# VoltMeter.net
KiCad netlist of a schematic drawn in EAGLE
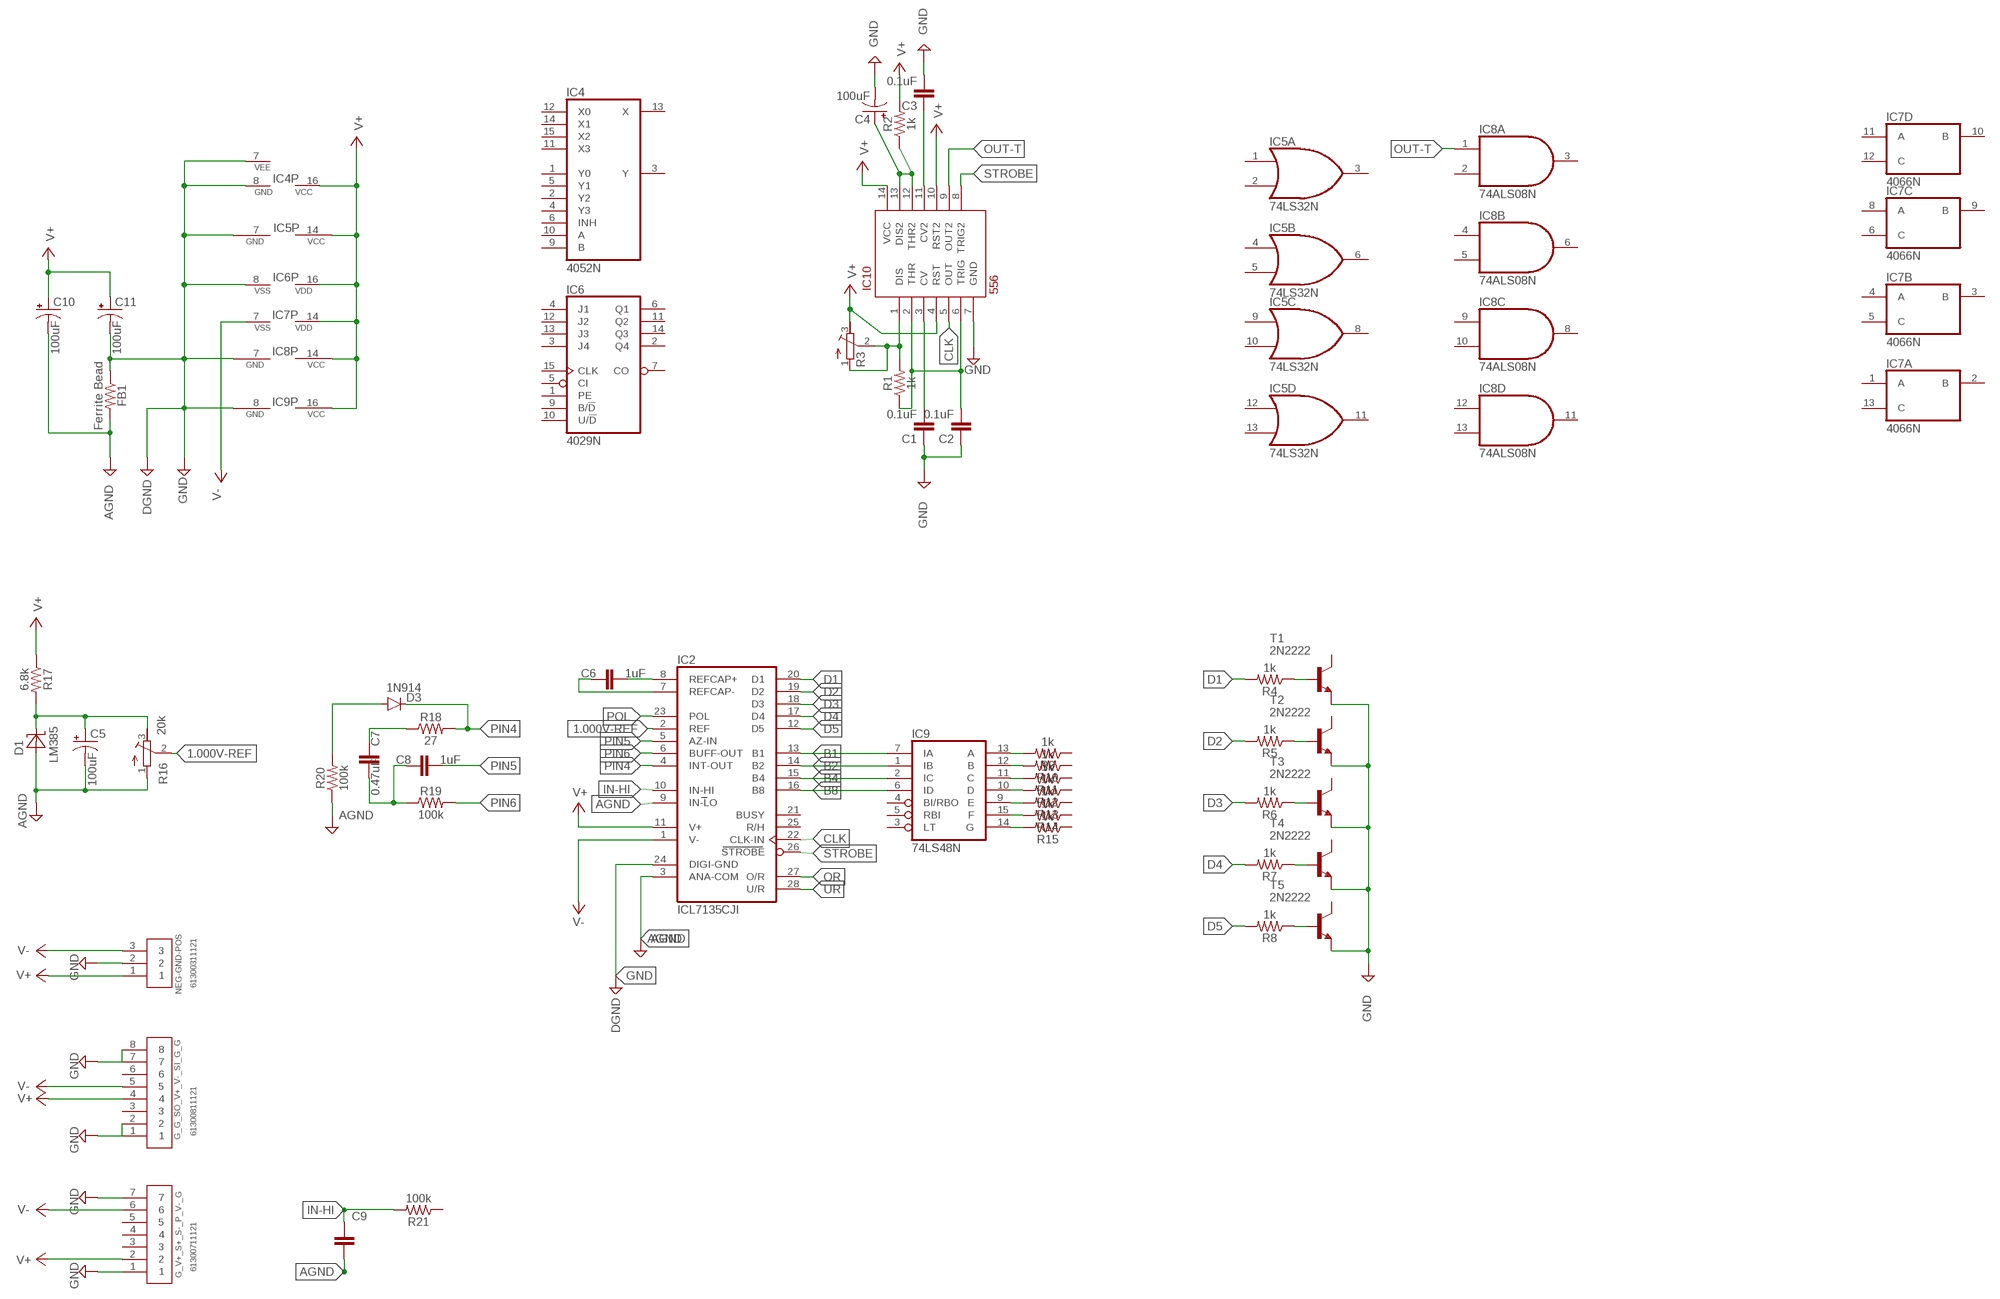
[diagram p0: schematic, sheet 1]

(export (version "E")
  (design (tool "Eeschema 10.0.6"))
  (components
    (comp (ref "C1")
      (value "0.1uF")
      (footprint "eagle-import:CAP-PTH-SMALL-KIT")
      (libsource (lib "eagle-import") (part "0.1UF-KIT-EZ-50V-20%"))
    )
    (comp (ref "C2")
      (value "0.1uF")
      (footprint "eagle-import:CAP-PTH-SMALL-KIT")
      (libsource (lib "eagle-import") (part "0.1UF-KIT-EZ-50V-20%"))
    )
    (comp (ref "C3")
      (value "0.1uF")
      (footprint "eagle-import:CAP-PTH-SMALL-KIT")
      (libsource (lib "eagle-import") (part "0.1UF-KIT-EZ-50V-20%"))
    )
    (comp (ref "C4")
      (value "100uF")
      (footprint "eagle-import:CPOL-RADIAL-2.5MM-6.5MM")
      (libsource (lib "eagle-import") (part "100UF-POLAR-RADIAL-2.5MM-25V-20%"))
    )
    (comp (ref "C5")
      (value "100uF")
      (footprint "eagle-import:CPOL-RADIAL-2.5MM-6.5MM")
      (libsource (lib "eagle-import") (part "100UF-POLAR-RADIAL-2.5MM-25V-20%"))
    )
    (comp (ref "C6")
      (value "1uF")
      (footprint "eagle-import:CAP-PTH-SMALL-KIT")
      (libsource (lib "eagle-import") (part "0.1UF-KIT-EZ-50V-20%"))
    )
    (comp (ref "C7")
      (value "0.47uF")
      (footprint "eagle-import:CAP-PTH-SMALL-KIT")
      (libsource (lib "eagle-import") (part "0.1UF-KIT-EZ-50V-20%"))
    )
    (comp (ref "C8")
      (value "1uF")
      (footprint "eagle-import:CAP-PTH-SMALL-KIT")
      (libsource (lib "eagle-import") (part "0.1UF-KIT-EZ-50V-20%"))
    )
    (comp (ref "C9")
      (value "0.1uF")
      (footprint "eagle-import:C5B2.5")
      (libsource (lib "eagle-import") (part "C5/2.5"))
    )
    (comp (ref "C10")
      (value "100uF")
      (footprint "eagle-import:CPOL-RADIAL-2.5MM-6.5MM")
      (libsource (lib "eagle-import") (part "100UF-POLAR-RADIAL-2.5MM-25V-20%"))
    )
    (comp (ref "C11")
      (value "100uF")
      (footprint "eagle-import:CPOL-RADIAL-2.5MM-6.5MM")
      (libsource (lib "eagle-import") (part "100UF-POLAR-RADIAL-2.5MM-25V-20%"))
    )
    (comp (ref "D1")
      (value "LM385")
      (footprint "eagle-import:TO-92")
      (libsource (lib "eagle-import") (part "LM385"))
    )
    (comp (ref "D3")
      (value "1N914")
      (footprint "eagle-import:DO35-7")
      (libsource (lib "eagle-import") (part "1N4148DO35-7"))
    )
    (comp (ref "FB1")
      (value "Ferrite Bead")
      (footprint "eagle-import:AXIAL-0.3")
      (libsource (lib "eagle-import") (part "1KOHM-HORIZ-1/4W-5%"))
    )
    (comp (ref "G_G_SO_V+_V-_SI_G_G")
      (value "61300811121")
      (footprint "eagle-import:61300811121")
      (fields
        (field (name "DIGI_KEY_PART_NUMBER") "732-5321-ND")
        (field (name "MANUFACTURER") "Wurth Electronics Inc.")
        (field (name "CREATED_BY") "PCBLayout.com")
      )
      (libsource (lib "eagle-import") (part "61300811121"))
    )
    (comp (ref "G_V+_S+_S-_P_V-_G")
      (value "61300711121")
      (footprint "eagle-import:61300711121")
      (fields
        (field (name "DIGI_KEY_PART_NUMBER") "732-5320-ND")
        (field (name "MANUFACTURER") "Wurth Electronics Inc.")
        (field (name "CREATED_BY") "PCBLayout.com")
      )
      (libsource (lib "eagle-import") (part "61300711121"))
    )
    (comp (ref "IC2")
      (value "ICL7135CJI")
      (footprint "eagle-import:DIL28-6")
      (libsource (lib "eagle-import") (part "ICL7135CJI"))
    )
    (comp (ref "IC4")
      (value "4052N")
      (footprint "eagle-import:DIL16")
      (libsource (lib "eagle-import") (part "4052N"))
    )
    (comp (ref "IC5")
      (value "74LS32N")
      (footprint "eagle-import:DIL14")
      (libsource (lib "eagle-import") (part "7432NLS"))
    )
    (comp (ref "IC6")
      (value "4029N")
      (footprint "eagle-import:DIL16")
      (libsource (lib "eagle-import") (part "4029N"))
    )
    (comp (ref "IC7")
      (value "4066N")
      (footprint "eagle-import:DIL14")
      (libsource (lib "eagle-import") (part "4066N"))
    )
    (comp (ref "IC8")
      (value "74ALS08N")
      (footprint "eagle-import:DIL14")
      (libsource (lib "eagle-import") (part "7408NALS"))
    )
    (comp (ref "IC9")
      (value "74LS48N")
      (footprint "eagle-import:DIL16")
      (libsource (lib "eagle-import") (part "7448NLS"))
    )
    (comp (ref "IC10")
      (value "556")
      (footprint "eagle-import:DIP14")
      (libsource (lib "eagle-import") (part "556"))
    )
    (comp (ref "NEG-GND-POS")
      (value "61300311121")
      (footprint "eagle-import:61300311121")
      (fields
        (field (name "DIGI_KEY_PART_NUMBER") "732-5316-ND")
        (field (name "MANUFACTURER") "Wurth Electronics Inc.")
        (field (name "CREATED_BY") "PCBLayout.com")
      )
      (libsource (lib "eagle-import") (part "61300311121"))
    )
    (comp (ref "R1")
      (value "1k")
      (footprint "eagle-import:AXIAL-0.3")
      (libsource (lib "eagle-import") (part "1KOHM-HORIZ-1/4W-1%"))
    )
    (comp (ref "R2")
      (value "1k")
      (footprint "eagle-import:AXIAL-0.3")
      (libsource (lib "eagle-import") (part "1KOHM-HORIZ-1/4W-1%"))
    )
    (comp (ref "R3")
      (value "R-TRIMM3299W")
      (footprint "eagle-import:RTRIM3299W")
      (libsource (lib "eagle-import") (part "R-TRIMM3299W"))
    )
    (comp (ref "R4")
      (value "1k")
      (footprint "eagle-import:AXIAL-0.3")
      (libsource (lib "eagle-import") (part "1KOHM-HORIZ-1/4W-1%"))
    )
    (comp (ref "R5")
      (value "1k")
      (footprint "eagle-import:AXIAL-0.3")
      (libsource (lib "eagle-import") (part "1KOHM-HORIZ-1/4W-1%"))
    )
    (comp (ref "R6")
      (value "1k")
      (footprint "eagle-import:AXIAL-0.3")
      (libsource (lib "eagle-import") (part "1KOHM-HORIZ-1/4W-1%"))
    )
    (comp (ref "R7")
      (value "1k")
      (footprint "eagle-import:AXIAL-0.3")
      (libsource (lib "eagle-import") (part "1KOHM-HORIZ-1/4W-1%"))
    )
    (comp (ref "R8")
      (value "1k")
      (footprint "eagle-import:AXIAL-0.3")
      (libsource (lib "eagle-import") (part "1KOHM-HORIZ-1/4W-1%"))
    )
    (comp (ref "R9")
      (value "1k")
      (footprint "eagle-import:AXIAL-0.3")
      (libsource (lib "eagle-import") (part "1KOHM-HORIZ-1/4W-1%"))
    )
    (comp (ref "R10")
      (value "1k")
      (footprint "eagle-import:AXIAL-0.3")
      (libsource (lib "eagle-import") (part "1KOHM-HORIZ-1/4W-1%"))
    )
    (comp (ref "R11")
      (value "1k")
      (footprint "eagle-import:AXIAL-0.3")
      (libsource (lib "eagle-import") (part "1KOHM-HORIZ-1/4W-1%"))
    )
    (comp (ref "R12")
      (value "1k")
      (footprint "eagle-import:AXIAL-0.3")
      (libsource (lib "eagle-import") (part "1KOHM-HORIZ-1/4W-1%"))
    )
    (comp (ref "R13")
      (value "1k")
      (footprint "eagle-import:AXIAL-0.3")
      (libsource (lib "eagle-import") (part "1KOHM-HORIZ-1/4W-1%"))
    )
    (comp (ref "R14")
      (value "1k")
      (footprint "eagle-import:AXIAL-0.3")
      (libsource (lib "eagle-import") (part "1KOHM-HORIZ-1/4W-1%"))
    )
    (comp (ref "R15")
      (value "1k")
      (footprint "eagle-import:AXIAL-0.3")
      (libsource (lib "eagle-import") (part "1KOHM-HORIZ-1/4W-1%"))
    )
    (comp (ref "R16")
      (value "20k")
      (footprint "eagle-import:RTRIM3299W")
      (libsource (lib "eagle-import") (part "R-TRIMM3299W"))
    )
    (comp (ref "R17")
      (value "6.8k")
      (footprint "eagle-import:AXIAL-0.3")
      (libsource (lib "eagle-import") (part "1KOHM-HORIZ-1/4W-1%"))
    )
    (comp (ref "R18")
      (value "27")
      (footprint "eagle-import:AXIAL-0.3")
      (libsource (lib "eagle-import") (part "1KOHM-HORIZ-1/4W-1%"))
    )
    (comp (ref "R19")
      (value "100k")
      (footprint "eagle-import:AXIAL-0.3")
      (libsource (lib "eagle-import") (part "1KOHM-HORIZ-1/4W-1%"))
    )
    (comp (ref "R20")
      (value "100k")
      (footprint "eagle-import:AXIAL-0.3")
      (libsource (lib "eagle-import") (part "1KOHM-HORIZ-1/4W-1%"))
    )
    (comp (ref "R21")
      (value "100k")
      (footprint "eagle-import:AXIAL-0.3")
      (libsource (lib "eagle-import") (part "1KOHM-HORIZ-1/4W-1%"))
    )
    (comp (ref "T1")
      (value "2N2222")
      (footprint "eagle-import:TO92-EBC-OVAL")
      (libsource (lib "eagle-import") (part "2N2222"))
    )
    (comp (ref "T2")
      (value "2N2222")
      (footprint "eagle-import:TO92-EBC-OVAL")
      (libsource (lib "eagle-import") (part "2N2222"))
    )
    (comp (ref "T3")
      (value "2N2222")
      (footprint "eagle-import:TO92-EBC-OVAL")
      (libsource (lib "eagle-import") (part "2N2222"))
    )
    (comp (ref "T4")
      (value "2N2222")
      (footprint "eagle-import:TO92-EBC-OVAL")
      (libsource (lib "eagle-import") (part "2N2222"))
    )
    (comp (ref "T5")
      (value "2N2222")
      (footprint "eagle-import:TO92-EBC-OVAL")
      (libsource (lib "eagle-import") (part "2N2222"))
    )
  )
  (nets
    (net (code "1") (name "1.000V-REF") (class "Default")
      (node (ref "IC2") (pin "2") (pinfunction "REF_2") (pintype "input"))
      (node (ref "R16") (pin "2") (pinfunction "S_2") (pintype "passive"))
    )
    (net (code "2") (name "AGND") (class "Default")
      (node (ref "C10") (pin "2") (pinfunction "-_2") (pintype "passive"))
      (node (ref "C5") (pin "2") (pinfunction "-_2") (pintype "passive"))
      (node (ref "C9") (pin "2") (pinfunction "2_2") (pintype "passive"))
      (node (ref "D1") (pin "+") (pinfunction "+_+") (pintype "passive"))
      (node (ref "FB1") (pin "P$2") (pinfunction "2_P$2") (pintype "passive"))
      (node (ref "IC2") (pin "3") (pinfunction "ANA-COM_3") (pintype "power_in"))
      (node (ref "IC2") (pin "9") (pinfunction "IN-LO_9") (pintype "input"))
      (node (ref "R16") (pin "1") (pinfunction "A_1") (pintype "passive"))
      (node (ref "R20") (pin "P$1") (pinfunction "1_P$1") (pintype "passive"))
    )
    (net (code "3") (name "B1") (class "Default")
      (node (ref "IC2") (pin "13") (pinfunction "B1_13") (pintype "output"))
      (node (ref "IC9") (pin "7") (pinfunction "IA_7") (pintype "input"))
    )
    (net (code "4") (name "B2") (class "Default")
      (node (ref "IC2") (pin "14") (pinfunction "B2_14") (pintype "output"))
      (node (ref "IC9") (pin "1") (pinfunction "IB_1") (pintype "input"))
    )
    (net (code "5") (name "B4") (class "Default")
      (node (ref "IC2") (pin "15") (pinfunction "B4_15") (pintype "output"))
      (node (ref "IC9") (pin "2") (pinfunction "IC_2") (pintype "input"))
    )
    (net (code "6") (name "B8") (class "Default")
      (node (ref "IC2") (pin "16") (pinfunction "B8_16") (pintype "output"))
      (node (ref "IC9") (pin "6") (pinfunction "ID_6") (pintype "input"))
    )
    (net (code "7") (name "CLK") (class "Default")
      (node (ref "IC10") (pin "5") (pinfunction "OUT_5") (pintype "bidirectional"))
      (node (ref "IC2") (pin "22") (pinfunction "CLK-IN_22") (pintype "input"))
    )
    (net (code "8") (name "D1") (class "Default")
      (node (ref "IC2") (pin "20") (pinfunction "D1_20") (pintype "tri_state"))
      (node (ref "R4") (pin "P$2") (pinfunction "2_P$2") (pintype "passive"))
    )
    (net (code "9") (name "D2") (class "Default")
      (node (ref "IC2") (pin "19") (pinfunction "D2_19") (pintype "tri_state"))
      (node (ref "R5") (pin "P$2") (pinfunction "2_P$2") (pintype "passive"))
    )
    (net (code "10") (name "D3") (class "Default")
      (node (ref "IC2") (pin "18") (pinfunction "D3_18") (pintype "tri_state"))
      (node (ref "R6") (pin "P$2") (pinfunction "2_P$2") (pintype "passive"))
    )
    (net (code "11") (name "D4") (class "Default")
      (node (ref "IC2") (pin "17") (pinfunction "D4_17") (pintype "tri_state"))
      (node (ref "R7") (pin "P$2") (pinfunction "2_P$2") (pintype "passive"))
    )
    (net (code "12") (name "D5") (class "Default")
      (node (ref "IC2") (pin "12") (pinfunction "D5_12") (pintype "tri_state"))
      (node (ref "R8") (pin "P$2") (pinfunction "2_P$2") (pintype "passive"))
    )
    (net (code "13") (name "GND") (class "Default")
      (node (ref "C1") (pin "1") (pinfunction "1_1") (pintype "passive"))
      (node (ref "C11") (pin "2") (pinfunction "-_2") (pintype "passive"))
      (node (ref "C2") (pin "1") (pinfunction "1_1") (pintype "passive"))
      (node (ref "C3") (pin "2") (pinfunction "2_2") (pintype "passive"))
      (node (ref "C4") (pin "2") (pinfunction "-_2") (pintype "passive"))
      (node (ref "FB1") (pin "P$1") (pinfunction "1_P$1") (pintype "passive"))
      (node (ref "G_G_SO_V+_V-_SI_G_G") (pin "1") (pinfunction "1_1") (pintype "passive"))
      (node (ref "G_G_SO_V+_V-_SI_G_G") (pin "2") (pinfunction "2_2") (pintype "passive"))
      (node (ref "G_G_SO_V+_V-_SI_G_G") (pin "7") (pinfunction "7_7") (pintype "passive"))
      (node (ref "G_G_SO_V+_V-_SI_G_G") (pin "8") (pinfunction "8_8") (pintype "passive"))
      (node (ref "G_V+_S+_S-_P_V-_G") (pin "1") (pinfunction "1_1") (pintype "passive"))
      (node (ref "G_V+_S+_S-_P_V-_G") (pin "7") (pinfunction "7_7") (pintype "passive"))
      (node (ref "IC10") (pin "7") (pinfunction "GND_7") (pintype "bidirectional"))
      (node (ref "IC2") (pin "24") (pinfunction "DIGI-GND_24") (pintype "power_in"))
      (node (ref "IC4") (pin "7") (pinfunction "VEE_7") (pintype "power_in"))
      (node (ref "IC4") (pin "8") (pinfunction "GND_8") (pintype "power_in"))
      (node (ref "IC5") (pin "7") (pinfunction "GND_7") (pintype "power_in"))
      (node (ref "IC6") (pin "8") (pinfunction "VSS_8") (pintype "power_in"))
      (node (ref "IC8") (pin "7") (pinfunction "GND_7") (pintype "power_in"))
      (node (ref "IC9") (pin "8") (pinfunction "GND_8") (pintype "power_in"))
      (node (ref "NEG-GND-POS") (pin "2") (pinfunction "2_2") (pintype "passive"))
      (node (ref "T1") (pin "E") (pinfunction "E_E") (pintype "passive"))
      (node (ref "T2") (pin "E") (pinfunction "E_E") (pintype "passive"))
      (node (ref "T3") (pin "E") (pinfunction "E_E") (pintype "passive"))
      (node (ref "T4") (pin "E") (pinfunction "E_E") (pintype "passive"))
      (node (ref "T5") (pin "E") (pinfunction "E_E") (pintype "passive"))
    )
    (net (code "14") (name "IN-HI") (class "Default")
      (node (ref "C9") (pin "1") (pinfunction "1_1") (pintype "passive"))
      (node (ref "IC2") (pin "10") (pinfunction "IN-HI_10") (pintype "input"))
      (node (ref "R21") (pin "P$2") (pinfunction "2_P$2") (pintype "passive"))
    )
    (net (code "15") (name "Net-(C4-+)") (class "Default")
      (node (ref "C4") (pin "1") (pinfunction "+_1") (pintype "passive"))
      (node (ref "IC10") (pin "12") (pinfunction "THR2_12") (pintype "bidirectional"))
      (node (ref "IC10") (pin "13") (pinfunction "DIS2_13") (pintype "bidirectional"))
      (node (ref "R2") (pin "P$1") (pinfunction "1_P$1") (pintype "passive"))
    )
    (net (code "16") (name "Net-(C5-+)") (class "Default")
      (node (ref "C5") (pin "1") (pinfunction "+_1") (pintype "passive"))
      (node (ref "D1") (pin "-") (pinfunction "-_-") (pintype "passive"))
      (node (ref "R16") (pin "3") (pinfunction "E_3") (pintype "passive"))
      (node (ref "R17") (pin "P$2") (pinfunction "2_P$2") (pintype "passive"))
    )
    (net (code "17") (name "Net-(IC2-REFCAP+)") (class "Default")
      (node (ref "C6") (pin "2") (pinfunction "2_2") (pintype "passive"))
      (node (ref "IC2") (pin "8") (pinfunction "REFCAP+_8") (pintype "passive"))
    )
    (net (code "18") (name "Net-(IC2-REFCAP-)") (class "Default")
      (node (ref "C6") (pin "1") (pinfunction "1_1") (pintype "passive"))
      (node (ref "IC2") (pin "7") (pinfunction "REFCAP-_7") (pintype "passive"))
    )
    (net (code "19") (name "Net-(IC9A-A)") (class "Default")
      (node (ref "IC9") (pin "13") (pinfunction "A_13") (pintype "output"))
      (node (ref "R9") (pin "P$2") (pinfunction "2_P$2") (pintype "passive"))
    )
    (net (code "20") (name "Net-(IC9A-B)") (class "Default")
      (node (ref "IC9") (pin "12") (pinfunction "B_12") (pintype "output"))
      (node (ref "R10") (pin "P$2") (pinfunction "2_P$2") (pintype "passive"))
    )
    (net (code "21") (name "Net-(IC9A-C)") (class "Default")
      (node (ref "IC9") (pin "11") (pinfunction "C_11") (pintype "output"))
      (node (ref "R11") (pin "P$2") (pinfunction "2_P$2") (pintype "passive"))
    )
    (net (code "22") (name "Net-(IC9A-D)") (class "Default")
      (node (ref "IC9") (pin "10") (pinfunction "D_10") (pintype "output"))
      (node (ref "R12") (pin "P$2") (pinfunction "2_P$2") (pintype "passive"))
    )
    (net (code "23") (name "Net-(IC9A-E)") (class "Default")
      (node (ref "IC9") (pin "9") (pinfunction "E_9") (pintype "output"))
      (node (ref "R13") (pin "P$2") (pinfunction "2_P$2") (pintype "passive"))
    )
    (net (code "24") (name "Net-(IC9A-F)") (class "Default")
      (node (ref "IC9") (pin "15") (pinfunction "F_15") (pintype "output"))
      (node (ref "R14") (pin "P$2") (pinfunction "2_P$2") (pintype "passive"))
    )
    (net (code "25") (name "Net-(IC9A-G)") (class "Default")
      (node (ref "IC9") (pin "14") (pinfunction "G_14") (pintype "output"))
      (node (ref "R15") (pin "P$2") (pinfunction "2_P$2") (pintype "passive"))
    )
    (net (code "26") (name "Net-(IC10-CV)") (class "Default")
      (node (ref "C1") (pin "2") (pinfunction "2_2") (pintype "passive"))
      (node (ref "IC10") (pin "3") (pinfunction "CV_3") (pintype "bidirectional"))
    )
    (net (code "27") (name "Net-(IC10-CV2)") (class "Default")
      (node (ref "C3") (pin "1") (pinfunction "1_1") (pintype "passive"))
      (node (ref "IC10") (pin "11") (pinfunction "CV2_11") (pintype "bidirectional"))
    )
    (net (code "28") (name "Net-(IC10-DIS)") (class "Default")
      (node (ref "IC10") (pin "1") (pinfunction "DIS_1") (pintype "bidirectional"))
      (node (ref "R1") (pin "P$2") (pinfunction "2_P$2") (pintype "passive"))
      (node (ref "R3") (pin "1") (pinfunction "A_1") (pintype "passive"))
      (node (ref "R3") (pin "2") (pinfunction "S_2") (pintype "passive"))
    )
    (net (code "29") (name "Net-(IC10-THR)") (class "Default")
      (node (ref "C2") (pin "2") (pinfunction "2_2") (pintype "passive"))
      (node (ref "IC10") (pin "2") (pinfunction "THR_2") (pintype "bidirectional"))
      (node (ref "IC10") (pin "6") (pinfunction "TRIG_6") (pintype "bidirectional"))
      (node (ref "R1") (pin "P$1") (pinfunction "1_P$1") (pintype "passive"))
    )
    (net (code "30") (name "Net-(R4-1)") (class "Default")
      (node (ref "R4") (pin "P$1") (pinfunction "1_P$1") (pintype "passive"))
      (node (ref "T1") (pin "B") (pinfunction "B_B") (pintype "passive"))
    )
    (net (code "31") (name "Net-(R5-1)") (class "Default")
      (node (ref "R5") (pin "P$1") (pinfunction "1_P$1") (pintype "passive"))
      (node (ref "T2") (pin "B") (pinfunction "B_B") (pintype "passive"))
    )
    (net (code "32") (name "Net-(R6-1)") (class "Default")
      (node (ref "R6") (pin "P$1") (pinfunction "1_P$1") (pintype "passive"))
      (node (ref "T3") (pin "B") (pinfunction "B_B") (pintype "passive"))
    )
    (net (code "33") (name "Net-(R7-1)") (class "Default")
      (node (ref "R7") (pin "P$1") (pinfunction "1_P$1") (pintype "passive"))
      (node (ref "T4") (pin "B") (pinfunction "B_B") (pintype "passive"))
    )
    (net (code "34") (name "Net-(R8-1)") (class "Default")
      (node (ref "R8") (pin "P$1") (pinfunction "1_P$1") (pintype "passive"))
      (node (ref "T5") (pin "B") (pinfunction "B_B") (pintype "passive"))
    )
    (net (code "35") (name "Net-(R18-1)") (class "Default")
      (node (ref "C7") (pin "1") (pinfunction "1_1") (pintype "passive"))
      (node (ref "R18") (pin "P$1") (pinfunction "1_P$1") (pintype "passive"))
    )
    (net (code "36") (name "Net-(R19-1)") (class "Default")
      (node (ref "C7") (pin "2") (pinfunction "2_2") (pintype "passive"))
      (node (ref "C8") (pin "1") (pinfunction "1_1") (pintype "passive"))
      (node (ref "R19") (pin "P$1") (pinfunction "1_P$1") (pintype "passive"))
    )
    (net (code "37") (name "Net-(R20-2)") (class "Default")
      (node (ref "D3") (pin "A") (pinfunction "A_A") (pintype "passive"))
      (node (ref "R20") (pin "P$2") (pinfunction "2_P$2") (pintype "passive"))
    )
    (net (code "38") (name "OR") (class "Default")
      (node (ref "IC2") (pin "27") (pinfunction "O/R_27") (pintype "output"))
    )
    (net (code "39") (name "OUT-T") (class "Default")
      (node (ref "IC10") (pin "9") (pinfunction "OUT2_9") (pintype "bidirectional"))
      (node (ref "IC8") (pin "1") (pinfunction "I0_1") (pintype "input"))
    )
    (net (code "40") (name "PIN4") (class "Default")
      (node (ref "D3") (pin "C") (pinfunction "C_C") (pintype "passive"))
      (node (ref "IC2") (pin "4") (pinfunction "INT-OUT_4") (pintype "output"))
      (node (ref "R18") (pin "P$2") (pinfunction "2_P$2") (pintype "passive"))
    )
    (net (code "41") (name "PIN5") (class "Default")
      (node (ref "C8") (pin "2") (pinfunction "2_2") (pintype "passive"))
      (node (ref "IC2") (pin "5") (pinfunction "AZ-IN_5") (pintype "input"))
    )
    (net (code "42") (name "PIN6") (class "Default")
      (node (ref "IC2") (pin "6") (pinfunction "BUFF-OUT_6") (pintype "output"))
      (node (ref "R19") (pin "P$2") (pinfunction "2_P$2") (pintype "passive"))
    )
    (net (code "43") (name "POL") (class "Default")
      (node (ref "IC2") (pin "23") (pinfunction "POL_23") (pintype "input"))
    )
    (net (code "44") (name "STROBE") (class "Default")
      (node (ref "IC10") (pin "8") (pinfunction "TRIG2_8") (pintype "bidirectional"))
      (node (ref "IC2") (pin "26") (pinfunction "STROBE_26") (pintype "output"))
    )
    (net (code "45") (name "UR") (class "Default")
      (node (ref "IC2") (pin "28") (pinfunction "U/R_28") (pintype "output"))
    )
    (net (code "46") (name "V+") (class "Default")
      (node (ref "C10") (pin "1") (pinfunction "+_1") (pintype "passive"))
      (node (ref "C11") (pin "1") (pinfunction "+_1") (pintype "passive"))
      (node (ref "G_G_SO_V+_V-_SI_G_G") (pin "4") (pinfunction "4_4") (pintype "passive"))
      (node (ref "G_V+_S+_S-_P_V-_G") (pin "2") (pinfunction "2_2") (pintype "passive"))
      (node (ref "IC10") (pin "10") (pinfunction "RST2_10") (pintype "bidirectional"))
      (node (ref "IC10") (pin "14") (pinfunction "VCC_14") (pintype "bidirectional"))
      (node (ref "IC10") (pin "4") (pinfunction "RST_4") (pintype "bidirectional"))
      (node (ref "IC2") (pin "11") (pinfunction "V+_11") (pintype "power_in"))
      (node (ref "IC4") (pin "16") (pinfunction "VCC_16") (pintype "power_in"))
      (node (ref "IC5") (pin "14") (pinfunction "VCC_14") (pintype "power_in"))
      (node (ref "IC6") (pin "16") (pinfunction "VDD_16") (pintype "power_in"))
      (node (ref "IC7") (pin "14") (pinfunction "VDD_14") (pintype "power_in"))
      (node (ref "IC8") (pin "14") (pinfunction "VCC_14") (pintype "power_in"))
      (node (ref "IC9") (pin "16") (pinfunction "VCC_16") (pintype "power_in"))
      (node (ref "NEG-GND-POS") (pin "1") (pinfunction "1_1") (pintype "passive"))
      (node (ref "R17") (pin "P$1") (pinfunction "1_P$1") (pintype "passive"))
      (node (ref "R2") (pin "P$2") (pinfunction "2_P$2") (pintype "passive"))
      (node (ref "R3") (pin "3") (pinfunction "E_3") (pintype "passive"))
    )
    (net (code "47") (name "V-") (class "Default")
      (node (ref "G_G_SO_V+_V-_SI_G_G") (pin "5") (pinfunction "5_5") (pintype "passive"))
      (node (ref "G_V+_S+_S-_P_V-_G") (pin "6") (pinfunction "6_6") (pintype "passive"))
      (node (ref "IC2") (pin "1") (pinfunction "V-_1") (pintype "power_in"))
      (node (ref "IC7") (pin "7") (pinfunction "VSS_7") (pintype "power_in"))
      (node (ref "NEG-GND-POS") (pin "3") (pinfunction "3_3") (pintype "passive"))
    )
    (net (code "48") (name "unconnected-(G_G_SO_V+_V-_SI_G_G-Pad3)") (class "Default")
      (node (ref "G_G_SO_V+_V-_SI_G_G") (pin "3") (pinfunction "3_3") (pintype "passive"))
    )
    (net (code "49") (name "unconnected-(G_G_SO_V+_V-_SI_G_G-Pad6)") (class "Default")
      (node (ref "G_G_SO_V+_V-_SI_G_G") (pin "6") (pinfunction "6_6") (pintype "passive"))
    )
    (net (code "50") (name "unconnected-(G_V+_S+_S-_P_V-_G-Pad3)") (class "Default")
      (node (ref "G_V+_S+_S-_P_V-_G") (pin "3") (pinfunction "3_3") (pintype "passive"))
    )
    (net (code "51") (name "unconnected-(G_V+_S+_S-_P_V-_G-Pad4)") (class "Default")
      (node (ref "G_V+_S+_S-_P_V-_G") (pin "4") (pinfunction "4_4") (pintype "passive"))
    )
    (net (code "52") (name "unconnected-(G_V+_S+_S-_P_V-_G-Pad5)") (class "Default")
      (node (ref "G_V+_S+_S-_P_V-_G") (pin "5") (pinfunction "5_5") (pintype "passive"))
    )
    (net (code "53") (name "unconnected-(IC2-BUSY-Pad21)") (class "Default")
      (node (ref "IC2") (pin "21") (pinfunction "BUSY_21") (pintype "output"))
    )
    (net (code "54") (name "unconnected-(IC2-R{slash}H-Pad25)") (class "Default")
      (node (ref "IC2") (pin "25") (pinfunction "R/H_25") (pintype "input"))
    )
    (net (code "55") (name "unconnected-(IC4A-A-Pad10)") (class "Default")
      (node (ref "IC4") (pin "10") (pinfunction "A_10") (pintype "input"))
    )
    (net (code "56") (name "unconnected-(IC4A-B-Pad9)") (class "Default")
      (node (ref "IC4") (pin "9") (pinfunction "B_9") (pintype "input"))
    )
    (net (code "57") (name "unconnected-(IC4A-INH-Pad6)") (class "Default")
      (node (ref "IC4") (pin "6") (pinfunction "INH_6") (pintype "input"))
    )
    (net (code "58") (name "unconnected-(IC4A-X-Pad13)") (class "Default")
      (node (ref "IC4") (pin "13") (pinfunction "X_13") (pintype "bidirectional"))
    )
    (net (code "59") (name "unconnected-(IC4A-X0-Pad12)") (class "Default")
      (node (ref "IC4") (pin "12") (pinfunction "X0_12") (pintype "bidirectional"))
    )
    (net (code "60") (name "unconnected-(IC4A-X1-Pad14)") (class "Default")
      (node (ref "IC4") (pin "14") (pinfunction "X1_14") (pintype "bidirectional"))
    )
    (net (code "61") (name "unconnected-(IC4A-X2-Pad15)") (class "Default")
      (node (ref "IC4") (pin "15") (pinfunction "X2_15") (pintype "bidirectional"))
    )
    (net (code "62") (name "unconnected-(IC4A-X3-Pad11)") (class "Default")
      (node (ref "IC4") (pin "11") (pinfunction "X3_11") (pintype "bidirectional"))
    )
    (net (code "63") (name "unconnected-(IC4A-Y-Pad3)") (class "Default")
      (node (ref "IC4") (pin "3") (pinfunction "Y_3") (pintype "bidirectional"))
    )
    (net (code "64") (name "unconnected-(IC4A-Y0-Pad1)") (class "Default")
      (node (ref "IC4") (pin "1") (pinfunction "Y0_1") (pintype "bidirectional"))
    )
    (net (code "65") (name "unconnected-(IC4A-Y1-Pad5)") (class "Default")
      (node (ref "IC4") (pin "5") (pinfunction "Y1_5") (pintype "bidirectional"))
    )
    (net (code "66") (name "unconnected-(IC4A-Y2-Pad2)") (class "Default")
      (node (ref "IC4") (pin "2") (pinfunction "Y2_2") (pintype "bidirectional"))
    )
    (net (code "67") (name "unconnected-(IC4A-Y3-Pad4)") (class "Default")
      (node (ref "IC4") (pin "4") (pinfunction "Y3_4") (pintype "bidirectional"))
    )
    (net (code "68") (name "unconnected-(IC5A-I0-Pad1)") (class "Default")
      (node (ref "IC5") (pin "1") (pinfunction "I0_1") (pintype "input"))
    )
    (net (code "69") (name "unconnected-(IC5A-I1-Pad2)") (class "Default")
      (node (ref "IC5") (pin "2") (pinfunction "I1_2") (pintype "input"))
    )
    (net (code "70") (name "unconnected-(IC5A-O-Pad3)") (class "Default")
      (node (ref "IC5") (pin "3") (pinfunction "O_3") (pintype "output"))
    )
    (net (code "71") (name "unconnected-(IC5B-I0-Pad4)") (class "Default")
      (node (ref "IC5") (pin "4") (pinfunction "I0_4") (pintype "input"))
    )
    (net (code "72") (name "unconnected-(IC5B-I1-Pad5)") (class "Default")
      (node (ref "IC5") (pin "5") (pinfunction "I1_5") (pintype "input"))
    )
    (net (code "73") (name "unconnected-(IC5B-O-Pad6)") (class "Default")
      (node (ref "IC5") (pin "6") (pinfunction "O_6") (pintype "output"))
    )
    (net (code "74") (name "unconnected-(IC5C-I0-Pad9)") (class "Default")
      (node (ref "IC5") (pin "9") (pinfunction "I0_9") (pintype "input"))
    )
    (net (code "75") (name "unconnected-(IC5C-I1-Pad10)") (class "Default")
      (node (ref "IC5") (pin "10") (pinfunction "I1_10") (pintype "input"))
    )
    (net (code "76") (name "unconnected-(IC5C-O-Pad8)") (class "Default")
      (node (ref "IC5") (pin "8") (pinfunction "O_8") (pintype "output"))
    )
    (net (code "77") (name "unconnected-(IC5D-I0-Pad12)") (class "Default")
      (node (ref "IC5") (pin "12") (pinfunction "I0_12") (pintype "input"))
    )
    (net (code "78") (name "unconnected-(IC5D-I1-Pad13)") (class "Default")
      (node (ref "IC5") (pin "13") (pinfunction "I1_13") (pintype "input"))
    )
    (net (code "79") (name "unconnected-(IC5D-O-Pad11)") (class "Default")
      (node (ref "IC5") (pin "11") (pinfunction "O_11") (pintype "output"))
    )
    (net (code "80") (name "unconnected-(IC6A-B{slash}~{D}-Pad9)") (class "Default")
      (node (ref "IC6") (pin "9") (pinfunction "B/~{D}_9") (pintype "input"))
    )
    (net (code "81") (name "unconnected-(IC6A-CI-Pad5)") (class "Default")
      (node (ref "IC6") (pin "5") (pinfunction "CI_5") (pintype "input"))
    )
    (net (code "82") (name "unconnected-(IC6A-CLK-Pad15)") (class "Default")
      (node (ref "IC6") (pin "15") (pinfunction "CLK_15") (pintype "input"))
    )
    (net (code "83") (name "unconnected-(IC6A-CO-Pad7)") (class "Default")
      (node (ref "IC6") (pin "7") (pinfunction "CO_7") (pintype "output"))
    )
    (net (code "84") (name "unconnected-(IC6A-J1-Pad4)") (class "Default")
      (node (ref "IC6") (pin "4") (pinfunction "J1_4") (pintype "input"))
    )
    (net (code "85") (name "unconnected-(IC6A-J2-Pad12)") (class "Default")
      (node (ref "IC6") (pin "12") (pinfunction "J2_12") (pintype "input"))
    )
    (net (code "86") (name "unconnected-(IC6A-J3-Pad13)") (class "Default")
      (node (ref "IC6") (pin "13") (pinfunction "J3_13") (pintype "input"))
    )
    (net (code "87") (name "unconnected-(IC6A-J4-Pad3)") (class "Default")
      (node (ref "IC6") (pin "3") (pinfunction "J4_3") (pintype "input"))
    )
    (net (code "88") (name "unconnected-(IC6A-PE-Pad1)") (class "Default")
      (node (ref "IC6") (pin "1") (pinfunction "PE_1") (pintype "input"))
    )
    (net (code "89") (name "unconnected-(IC6A-Q1-Pad6)") (class "Default")
      (node (ref "IC6") (pin "6") (pinfunction "Q1_6") (pintype "output"))
    )
    (net (code "90") (name "unconnected-(IC6A-Q2-Pad11)") (class "Default")
      (node (ref "IC6") (pin "11") (pinfunction "Q2_11") (pintype "output"))
    )
    (net (code "91") (name "unconnected-(IC6A-Q3-Pad14)") (class "Default")
      (node (ref "IC6") (pin "14") (pinfunction "Q3_14") (pintype "output"))
    )
    (net (code "92") (name "unconnected-(IC6A-Q4-Pad2)") (class "Default")
      (node (ref "IC6") (pin "2") (pinfunction "Q4_2") (pintype "output"))
    )
    (net (code "93") (name "unconnected-(IC6A-U{slash}~{D}-Pad10)") (class "Default")
      (node (ref "IC6") (pin "10") (pinfunction "U/~{D}_10") (pintype "input"))
    )
    (net (code "94") (name "unconnected-(IC7A-A-Pad1)") (class "Default")
      (node (ref "IC7") (pin "1") (pinfunction "A_1") (pintype "tri_state"))
    )
    (net (code "95") (name "unconnected-(IC7A-B-Pad2)") (class "Default")
      (node (ref "IC7") (pin "2") (pinfunction "B_2") (pintype "tri_state"))
    )
    (net (code "96") (name "unconnected-(IC7A-C-Pad13)") (class "Default")
      (node (ref "IC7") (pin "13") (pinfunction "C_13") (pintype "input"))
    )
    (net (code "97") (name "unconnected-(IC7B-A-Pad4)") (class "Default")
      (node (ref "IC7") (pin "4") (pinfunction "A_4") (pintype "tri_state"))
    )
    (net (code "98") (name "unconnected-(IC7B-B-Pad3)") (class "Default")
      (node (ref "IC7") (pin "3") (pinfunction "B_3") (pintype "tri_state"))
    )
    (net (code "99") (name "unconnected-(IC7B-C-Pad5)") (class "Default")
      (node (ref "IC7") (pin "5") (pinfunction "C_5") (pintype "input"))
    )
    (net (code "100") (name "unconnected-(IC7C-A-Pad8)") (class "Default")
      (node (ref "IC7") (pin "8") (pinfunction "A_8") (pintype "tri_state"))
    )
    (net (code "101") (name "unconnected-(IC7C-B-Pad9)") (class "Default")
      (node (ref "IC7") (pin "9") (pinfunction "B_9") (pintype "tri_state"))
    )
    (net (code "102") (name "unconnected-(IC7C-C-Pad6)") (class "Default")
      (node (ref "IC7") (pin "6") (pinfunction "C_6") (pintype "input"))
    )
    (net (code "103") (name "unconnected-(IC7D-A-Pad11)") (class "Default")
      (node (ref "IC7") (pin "11") (pinfunction "A_11") (pintype "tri_state"))
    )
    (net (code "104") (name "unconnected-(IC7D-B-Pad10)") (class "Default")
      (node (ref "IC7") (pin "10") (pinfunction "B_10") (pintype "tri_state"))
    )
    (net (code "105") (name "unconnected-(IC7D-C-Pad12)") (class "Default")
      (node (ref "IC7") (pin "12") (pinfunction "C_12") (pintype "input"))
    )
    (net (code "106") (name "unconnected-(IC8A-I1-Pad2)") (class "Default")
      (node (ref "IC8") (pin "2") (pinfunction "I1_2") (pintype "input"))
    )
    (net (code "107") (name "unconnected-(IC8A-O-Pad3)") (class "Default")
      (node (ref "IC8") (pin "3") (pinfunction "O_3") (pintype "output"))
    )
    (net (code "108") (name "unconnected-(IC8B-I0-Pad4)") (class "Default")
      (node (ref "IC8") (pin "4") (pinfunction "I0_4") (pintype "input"))
    )
    (net (code "109") (name "unconnected-(IC8B-I1-Pad5)") (class "Default")
      (node (ref "IC8") (pin "5") (pinfunction "I1_5") (pintype "input"))
    )
    (net (code "110") (name "unconnected-(IC8B-O-Pad6)") (class "Default")
      (node (ref "IC8") (pin "6") (pinfunction "O_6") (pintype "output"))
    )
    (net (code "111") (name "unconnected-(IC8C-I0-Pad9)") (class "Default")
      (node (ref "IC8") (pin "9") (pinfunction "I0_9") (pintype "input"))
    )
    (net (code "112") (name "unconnected-(IC8C-I1-Pad10)") (class "Default")
      (node (ref "IC8") (pin "10") (pinfunction "I1_10") (pintype "input"))
    )
    (net (code "113") (name "unconnected-(IC8C-O-Pad8)") (class "Default")
      (node (ref "IC8") (pin "8") (pinfunction "O_8") (pintype "output"))
    )
    (net (code "114") (name "unconnected-(IC8D-I0-Pad12)") (class "Default")
      (node (ref "IC8") (pin "12") (pinfunction "I0_12") (pintype "input"))
    )
    (net (code "115") (name "unconnected-(IC8D-I1-Pad13)") (class "Default")
      (node (ref "IC8") (pin "13") (pinfunction "I1_13") (pintype "input"))
    )
    (net (code "116") (name "unconnected-(IC8D-O-Pad11)") (class "Default")
      (node (ref "IC8") (pin "11") (pinfunction "O_11") (pintype "output"))
    )
    (net (code "117") (name "unconnected-(IC9A-BI{slash}RBO-Pad4)") (class "Default")
      (node (ref "IC9") (pin "4") (pinfunction "BI/RBO_4") (pintype "input"))
    )
    (net (code "118") (name "unconnected-(IC9A-LT-Pad3)") (class "Default")
      (node (ref "IC9") (pin "3") (pinfunction "LT_3") (pintype "input"))
    )
    (net (code "119") (name "unconnected-(IC9A-RBI-Pad5)") (class "Default")
      (node (ref "IC9") (pin "5") (pinfunction "RBI_5") (pintype "input"))
    )
    (net (code "120") (name "unconnected-(R9-1-PadP$1)") (class "Default")
      (node (ref "R9") (pin "P$1") (pinfunction "1_P$1") (pintype "passive"))
    )
    (net (code "121") (name "unconnected-(R10-1-PadP$1)") (class "Default")
      (node (ref "R10") (pin "P$1") (pinfunction "1_P$1") (pintype "passive"))
    )
    (net (code "122") (name "unconnected-(R11-1-PadP$1)") (class "Default")
      (node (ref "R11") (pin "P$1") (pinfunction "1_P$1") (pintype "passive"))
    )
    (net (code "123") (name "unconnected-(R12-1-PadP$1)") (class "Default")
      (node (ref "R12") (pin "P$1") (pinfunction "1_P$1") (pintype "passive"))
    )
    (net (code "124") (name "unconnected-(R13-1-PadP$1)") (class "Default")
      (node (ref "R13") (pin "P$1") (pinfunction "1_P$1") (pintype "passive"))
    )
    (net (code "125") (name "unconnected-(R14-1-PadP$1)") (class "Default")
      (node (ref "R14") (pin "P$1") (pinfunction "1_P$1") (pintype "passive"))
    )
    (net (code "126") (name "unconnected-(R15-1-PadP$1)") (class "Default")
      (node (ref "R15") (pin "P$1") (pinfunction "1_P$1") (pintype "passive"))
    )
    (net (code "127") (name "unconnected-(R21-1-PadP$1)") (class "Default")
      (node (ref "R21") (pin "P$1") (pinfunction "1_P$1") (pintype "passive"))
    )
    (net (code "128") (name "unconnected-(T1-PadC)") (class "Default")
      (node (ref "T1") (pin "C") (pinfunction "C_C") (pintype "passive"))
    )
    (net (code "129") (name "unconnected-(T2-PadC)") (class "Default")
      (node (ref "T2") (pin "C") (pinfunction "C_C") (pintype "passive"))
    )
    (net (code "130") (name "unconnected-(T3-PadC)") (class "Default")
      (node (ref "T3") (pin "C") (pinfunction "C_C") (pintype "passive"))
    )
    (net (code "131") (name "unconnected-(T4-PadC)") (class "Default")
      (node (ref "T4") (pin "C") (pinfunction "C_C") (pintype "passive"))
    )
    (net (code "132") (name "unconnected-(T5-PadC)") (class "Default")
      (node (ref "T5") (pin "C") (pinfunction "C_C") (pintype "passive"))
    )
  )
)
